# LB-char-coilDriver.net
KiCad netlist of a schematic drawn in Altium Designer
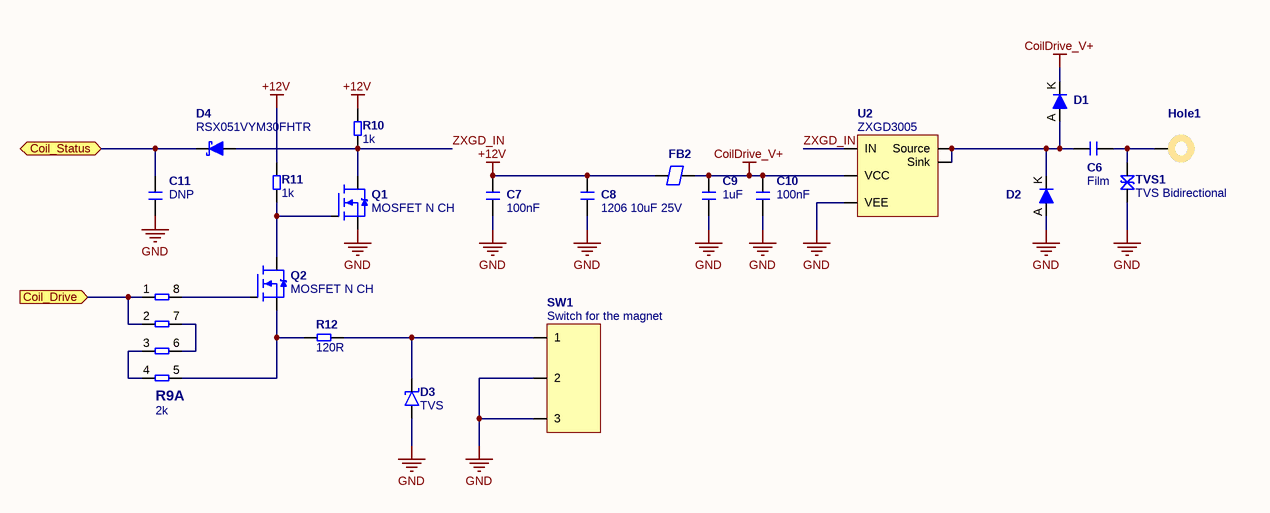
[diagram p0: LB-char-coilDriver.SchDoc]

(export (version "E")
  (design (tool "Eeschema 10.0.6"))
  (components
    (comp (ref "C6")
      (value "Film")
      (footprint "Cap Film 5mm pitch, 7.2x7.2mm")
      (libsource (lib "wes") (part "Capacitor - Film"))
    )
    (comp (ref "C7")
      (value "100nF")
      (footprint "C0603_N")
      (description "Capacitor MLCC")
      (fields
        (field (name "MANUFACTURER") "Yageo")
        (field (name "MANUFACTURER PART NUMBER") "CC0603KRX7R9BB104")
      )
      (libsource (lib "wes") (part "Capacitor"))
    )
    (comp (ref "C8")
      (value "1206 10uF 25V")
      (footprint "C1206_N")
      (description "Capacitor MLCC")
      (fields
        (field (name "MANUFACTURER") "Yageo")
        (field (name "MANUFACTURER PART NUMBER") "CC0603KRX7R9BB104")
      )
      (libsource (lib "wes") (part "Capacitor"))
    )
    (comp (ref "C9")
      (value "1uF")
      (footprint "C0603_N")
      (description "Capacitor MLCC")
      (fields
        (field (name "MANUFACTURER") "Yageo")
        (field (name "MANUFACTURER PART NUMBER") "CC0603KRX7R9BB104")
      )
      (libsource (lib "wes") (part "Capacitor"))
    )
    (comp (ref "C10")
      (value "100nF")
      (footprint "C0603_N")
      (description "Capacitor MLCC")
      (fields
        (field (name "MANUFACTURER") "Yageo")
        (field (name "MANUFACTURER PART NUMBER") "CC0603KRX7R9BB104")
      )
      (libsource (lib "wes") (part "Capacitor"))
    )
    (comp (ref "C11")
      (value "DNP")
      (footprint "C0603_N")
      (description "Capacitor MLCC")
      (fields
        (field (name "MANUFACTURER") "Yageo")
        (field (name "MANUFACTURER PART NUMBER") "CC0603KRX7R9BB104")
      )
      (libsource (lib "wes") (part "Capacitor"))
    )
    (comp (ref "D1") (value "RSX051VYM30FHTR") (footprint "SOD323F") (libsource (lib "wes") (part "Diode")))
    (comp (ref "D2") (value "RSX051VYM30FHTR") (footprint "SOD323F") (libsource (lib "wes") (part "Diode")))
    (comp (ref "D3") (value "TVS") (footprint "SOD323F-Comchip Variant") (libsource (lib "wes") (part "TVS")))
    (comp (ref "D4")
      (value "RSX051VYM30FHTR")
      (footprint "SOD323F")
      (libsource (lib "wes") (part "Diode Schottky"))
    )
    (comp (ref "FB2")
      (value "Ferrite Bead")
      (footprint "F0603_N")
      (libsource (lib "wes") (part "Ferrite Bead"))
    )
    (comp (ref "Hole1")
      (value "Hole")
      (footprint "Insert-Thread-SMD-M2")
      (libsource (lib "wes") (part "Hole"))
    )
    (comp (ref "Q1") (value "MOSFET N CH") (footprint "SOT23_N") (libsource (lib "wes") (part "MOSFET N CH")))
    (comp (ref "Q2") (value "MOSFET N CH") (footprint "SOT23_N") (libsource (lib "wes") (part "MOSFET N CH")))
    (comp (ref "R9")
      (value "; 2k")
      (footprint "YC164")
      (fields (field (name "Comment") "; 2k"))
      (libsource (lib "wes") (part "Resistor Array - 4P"))
    )
    (comp (ref "R10")
      (value "1k")
      (footprint "R0603")
      (fields (field (name "PUBLISHER") "Altium Limited"))
      (libsource (lib "wes") (part "Resistor"))
    )
    (comp (ref "R11")
      (value "1k")
      (footprint "R0603")
      (fields (field (name "PUBLISHER") "Altium Limited"))
      (libsource (lib "wes") (part "Resistor"))
    )
    (comp (ref "R12")
      (value "120R")
      (footprint "R0603")
      (fields (field (name "PUBLISHER") "Altium Limited"))
      (libsource (lib "wes") (part "Resistor"))
    )
    (comp (ref "SW1")
      (value "Switch for the magnet")
      (footprint "Linobyte - MagnetSwitch")
      (libsource (lib "wes") (part "Linobyte - MagnetSwitch"))
    )
    (comp (ref "TVS1")
      (value "TVS Bidirectional")
      (footprint "DO214AC SMA")
      (libsource (lib "wes") (part "TVS Bidirectional"))
    )
    (comp (ref "U2") (value "ZXGD3005") (footprint "SOT23-6_N") (libsource (lib "wes") (part "ZXGD3005")))
  )
  (nets
    (net (code "1") (name "+12V") (class "Default")
      (node (ref "C7") (pin "1") (pintype "passive"))
      (node (ref "C8") (pin "1") (pintype "passive"))
      (node (ref "FB2") (pin "2") (pinfunction "2_2") (pintype "passive"))
      (node (ref "R10") (pin "2") (pinfunction "2_2") (pintype "passive"))
      (node (ref "R11") (pin "2") (pinfunction "2_2") (pintype "passive"))
    )
    (net (code "2") (name "/Coil_Drive") (class "Default")
      (node (ref "R9") (pin "1") (pinfunction "1_1") (pintype "passive"))
      (node (ref "R9") (pin "2") (pinfunction "2_2") (pintype "passive"))
    )
    (net (code "3") (name "/Coil_Status") (class "Default")
      (node (ref "C11") (pin "1") (pintype "passive"))
      (node (ref "D4") (pin "K") (pinfunction "K_K") (pintype "passive"))
    )
    (net (code "4") (name "/ZXGD_IN") (class "Default")
      (node (ref "D4") (pin "A") (pinfunction "A_A") (pintype "passive"))
      (node (ref "Q1") (pin "2") (pinfunction "D_2") (pintype "passive"))
      (node (ref "R10") (pin "1") (pinfunction "1_1") (pintype "passive"))
      (node (ref "U2") (pin "2") (pinfunction "IN_2") (pintype "passive"))
    )
    (net (code "5") (name "CoilDrive_V+") (class "Default")
      (node (ref "C10") (pin "1") (pintype "passive"))
      (node (ref "C9") (pin "1") (pintype "passive"))
      (node (ref "D1") (pin "K") (pinfunction "K_K") (pintype "passive"))
      (node (ref "FB2") (pin "1") (pinfunction "1_1") (pintype "passive"))
      (node (ref "U2") (pin "1") (pinfunction "VCC_1") (pintype "passive"))
    )
    (net (code "6") (name "GND") (class "Default")
      (node (ref "C10") (pin "2") (pintype "passive"))
      (node (ref "C11") (pin "2") (pintype "passive"))
      (node (ref "C7") (pin "2") (pintype "passive"))
      (node (ref "C8") (pin "2") (pintype "passive"))
      (node (ref "C9") (pin "2") (pintype "passive"))
      (node (ref "D2") (pin "A") (pinfunction "A_A") (pintype "passive"))
      (node (ref "D3") (pin "1") (pinfunction "1_1") (pintype "passive"))
      (node (ref "Q1") (pin "3") (pinfunction "S_3") (pintype "passive"))
      (node (ref "SW1") (pin "2") (pinfunction "2_2") (pintype "passive"))
      (node (ref "SW1") (pin "3") (pinfunction "3_3") (pintype "passive"))
      (node (ref "TVS1") (pin "2") (pinfunction "2_2") (pintype "passive"))
      (node (ref "U2") (pin "3") (pinfunction "VEE_3") (pintype "passive"))
    )
    (net (code "7") (name "Net-(C6-Pad1)") (class "Default")
      (node (ref "C6") (pin "1") (pintype "passive"))
      (node (ref "Hole1") (pin "1") (pinfunction "1_1") (pintype "passive"))
      (node (ref "TVS1") (pin "1") (pinfunction "1_1") (pintype "passive"))
    )
    (net (code "8") (name "Net-(D3-Pad2)") (class "Default")
      (node (ref "D3") (pin "2") (pinfunction "2_2") (pintype "passive"))
      (node (ref "R12") (pin "2") (pinfunction "2_2") (pintype "passive"))
      (node (ref "SW1") (pin "1") (pinfunction "1_1") (pintype "passive"))
    )
    (net (code "9") (name "Net-(Q1-G)") (class "Default")
      (node (ref "Q1") (pin "1") (pinfunction "G_1") (pintype "passive"))
      (node (ref "Q2") (pin "2") (pinfunction "D_2") (pintype "passive"))
      (node (ref "R11") (pin "1") (pinfunction "1_1") (pintype "passive"))
    )
    (net (code "10") (name "Net-(Q2-G)") (class "Default")
      (node (ref "Q2") (pin "1") (pinfunction "G_1") (pintype "passive"))
      (node (ref "R9") (pin "8") (pinfunction "8_8") (pintype "passive"))
    )
    (net (code "11") (name "Net-(Q2-S)") (class "Default")
      (node (ref "Q2") (pin "3") (pinfunction "S_3") (pintype "passive"))
      (node (ref "R12") (pin "1") (pinfunction "1_1") (pintype "passive"))
      (node (ref "R9") (pin "5") (pinfunction "5_5") (pintype "passive"))
    )
    (net (code "12") (name "Net-(R9-Pad3)") (class "Default")
      (node (ref "R9") (pin "3") (pinfunction "3_3") (pintype "passive"))
      (node (ref "R9") (pin "4") (pinfunction "4_4") (pintype "passive"))
    )
    (net (code "13") (name "Net-(R9-Pad6)") (class "Default")
      (node (ref "R9") (pin "6") (pinfunction "6_6") (pintype "passive"))
      (node (ref "R9") (pin "7") (pinfunction "7_7") (pintype "passive"))
    )
    (net (code "14") (name "Net-(U2-Sink)") (class "Default")
      (node (ref "C6") (pin "2") (pintype "passive"))
      (node (ref "D1") (pin "A") (pinfunction "A_A") (pintype "passive"))
      (node (ref "D2") (pin "K") (pinfunction "K_K") (pintype "passive"))
      (node (ref "U2") (pin "4") (pinfunction "Sink_4") (pintype "passive"))
      (node (ref "U2") (pin "6") (pinfunction "Source_6") (pintype "passive"))
    )
  )
)
